# Multiplexers.net
KiCad netlist of a schematic drawn in Altium Designer
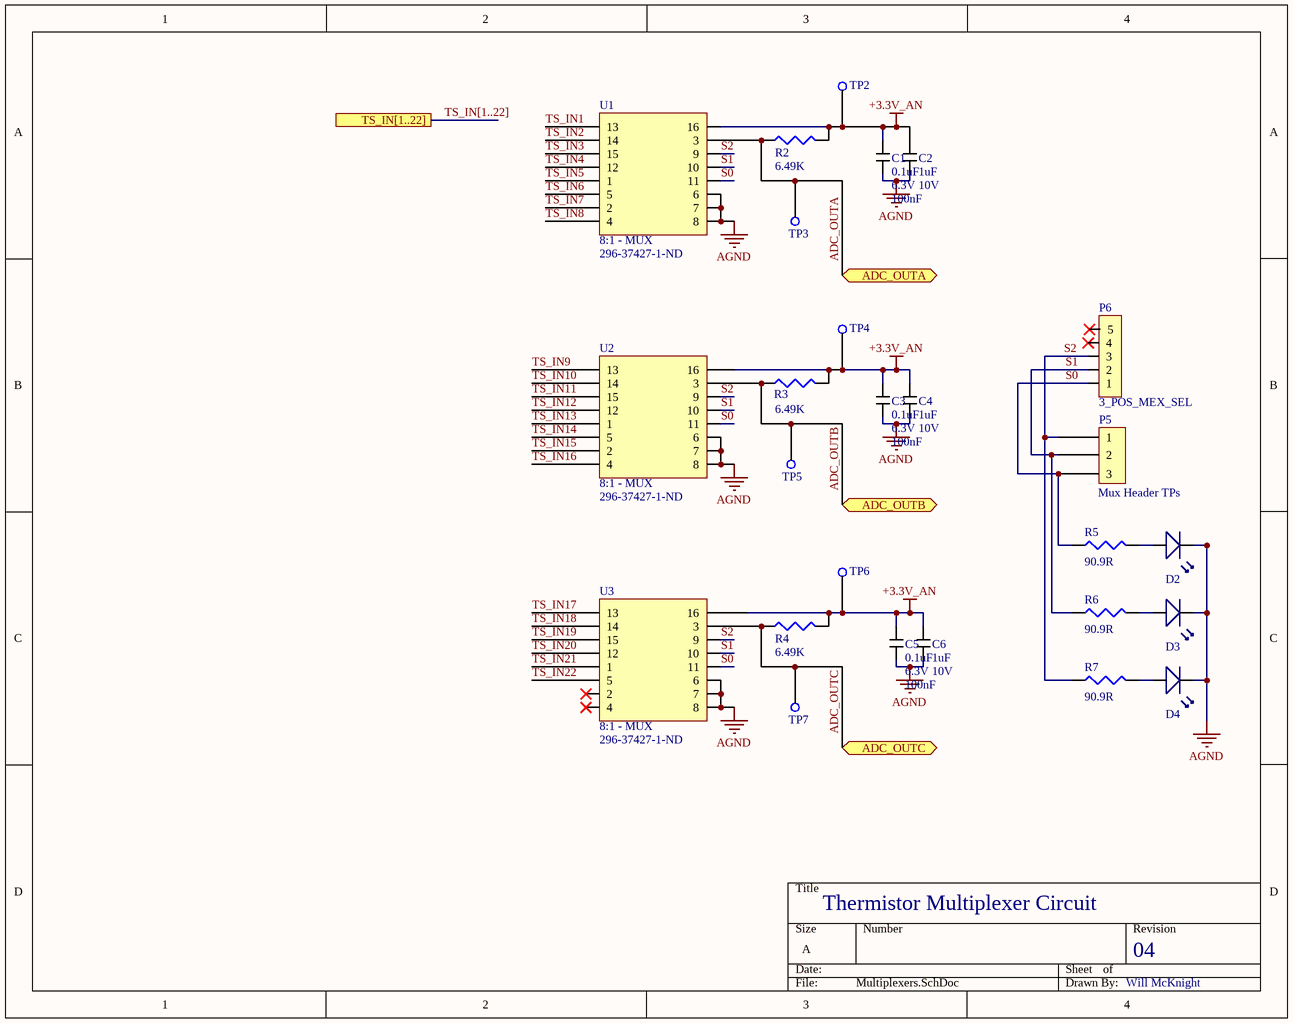
[diagram p0: Multiplexers.SchDoc]

(export (version "E")
  (design (tool "Eeschema 10.0.6"))
  (components
    (comp (ref "C1")
      (value "0.1uF")
      (footprint "0.1uF Bypass Capacitor")
      (description "0.1uF Bypass Cap")
      (fields
        (field (name "MANUFACTURER") "KEMET")
        (field (name "MANUFACTURER PART NUMBER") "C0603C104K9RACTU")
        (field (name "VOLTAGE RATING") "6.3V")
        (field (name "CAPACITANCE") "100nF")
      )
      (libsource (lib "Schematic_Library") (part "0.1uF Cap"))
    )
    (comp (ref "C2")
      (value "1uF")
      (footprint "1UF_SAMSUNG")
      (description "1uF Samsung Cap")
      (fields
        (field (name "MANUFACTURER") "Samsung")
        (field (name "MANUFACTURER PART NUMBER") "CL10B105KP8NNNC")
        (field (name "CAPACITANCE") "1uF")
        (field (name "VOLTAGE RATING") "10V")
      )
      (libsource (lib "Schematic_Library") (part "1uF Samsung Cap"))
    )
    (comp (ref "C3")
      (value "0.1uF")
      (footprint "0.1uF Bypass Capacitor")
      (description "0.1uF Bypass Cap")
      (fields
        (field (name "MANUFACTURER") "KEMET")
        (field (name "MANUFACTURER PART NUMBER") "C0603C104K9RACTU")
        (field (name "VOLTAGE RATING") "6.3V")
        (field (name "CAPACITANCE") "100nF")
      )
      (libsource (lib "Schematic_Library") (part "0.1uF Cap"))
    )
    (comp (ref "C4")
      (value "1uF")
      (footprint "1UF_SAMSUNG")
      (description "1uF Samsung Cap")
      (fields
        (field (name "MANUFACTURER") "Samsung")
        (field (name "MANUFACTURER PART NUMBER") "CL10B105KP8NNNC")
        (field (name "CAPACITANCE") "1uF")
        (field (name "VOLTAGE RATING") "10V")
      )
      (libsource (lib "Schematic_Library") (part "1uF Samsung Cap"))
    )
    (comp (ref "C5")
      (value "0.1uF")
      (footprint "0.1uF Bypass Capacitor")
      (description "0.1uF Bypass Cap")
      (fields
        (field (name "MANUFACTURER") "KEMET")
        (field (name "MANUFACTURER PART NUMBER") "C0603C104K9RACTU")
        (field (name "VOLTAGE RATING") "6.3V")
        (field (name "CAPACITANCE") "100nF")
      )
      (libsource (lib "Schematic_Library") (part "0.1uF Cap"))
    )
    (comp (ref "C6")
      (value "1uF")
      (footprint "1UF_SAMSUNG")
      (description "1uF Samsung Cap")
      (fields
        (field (name "MANUFACTURER") "Samsung")
        (field (name "MANUFACTURER PART NUMBER") "CL10B105KP8NNNC")
        (field (name "CAPACITANCE") "1uF")
        (field (name "VOLTAGE RATING") "10V")
      )
      (libsource (lib "Schematic_Library") (part "1uF Samsung Cap"))
    )
    (comp (ref "D2")
      (value "LED")
      (footprint "Green_SMD_LED")
      (fields
        (field (name "MANUFACTURER") "Dialight")
        (field (name "MANUFACTURER PART NUMBER") "5988070107F")
      )
      (libsource (lib "Schematic_Library") (part "GREEN_LED"))
    )
    (comp (ref "D3")
      (value "LED")
      (footprint "Green_SMD_LED")
      (fields
        (field (name "MANUFACTURER") "Dialight")
        (field (name "MANUFACTURER PART NUMBER") "5988070107F")
      )
      (libsource (lib "Schematic_Library") (part "GREEN_LED"))
    )
    (comp (ref "D4")
      (value "LED")
      (footprint "Green_SMD_LED")
      (fields
        (field (name "MANUFACTURER") "Dialight")
        (field (name "MANUFACTURER PART NUMBER") "5988070107F")
      )
      (libsource (lib "Schematic_Library") (part "GREEN_LED"))
    )
    (comp (ref "P5")
      (value "3 POS Mux Select Header")
      (footprint "Mux Select 3 Pos Header Pin")
      (description "Mux Sel Header TP")
      (fields
        (field (name "MANUFACTURER") "Adam Equipment")
        (field (name "MANUFACTURER PART NUMBER") "PH1RA-03-UA")
      )
      (libsource (lib "Schematic_Library") (part "3 POS Mux Select Header"))
    )
    (comp (ref "P6")
      (value "3_POS_MEX_SEL")
      (footprint "3POS_MUX_SEL")
      (description "Connector Header Surface Mount, Right Angle 3 position 0.049\" (1.25mm)")
      (fields (field (name "MANUFACTURER") "Molex") (field (name "MANUFACTURER PART NUMBER") "505567-0371"))
      (libsource (lib "Schematic_Library") (part "3_POS_MEX_SEL"))
    )
    (comp (ref "R2")
      (value "6.49kOhm SMD Resistor")
      (footprint "RESC2012X06N")
      (fields
        (field (name "MANUFACTURER") "Panasonic")
        (field (name "MANUFACTURER PART NUMBER") "ERA6AEB6491V")
        (field (name "TOLERANCE") "0.1%")
        (field (name "RESISTANCE") "6.49K")
      )
      (libsource (lib "Schematic_Library") (part "6.49kOhm SMD Resistor"))
    )
    (comp (ref "R3")
      (value "6.49kOhm SMD Resistor")
      (footprint "RESC2012X06N")
      (fields
        (field (name "MANUFACTURER") "Panasonic")
        (field (name "MANUFACTURER PART NUMBER") "ERA6AEB6491V")
        (field (name "TOLERANCE") "0.1%")
        (field (name "RESISTANCE") "6.49K")
      )
      (libsource (lib "Schematic_Library") (part "6.49kOhm SMD Resistor"))
    )
    (comp (ref "R4")
      (value "6.49kOhm SMD Resistor")
      (footprint "RESC2012X06N")
      (fields
        (field (name "MANUFACTURER") "Panasonic")
        (field (name "MANUFACTURER PART NUMBER") "ERA6AEB6491V")
        (field (name "TOLERANCE") "0.1%")
        (field (name "RESISTANCE") "6.49K")
      )
      (libsource (lib "Schematic_Library") (part "6.49kOhm SMD Resistor"))
    )
    (comp (ref "R5")
      (value "Green_LED_Res")
      (footprint "Green_LED_Resistor_90.9")
      (fields
        (field (name "MANUFACTURER") "Panasonic")
        (field (name "MANUFACTURER PART NUMBER") "ERJ-1GNF90R9C")
        (field (name "TOLERANCE") "1%")
        (field (name "RESISTANCE") "90.9R")
      )
      (libsource (lib "Schematic_Library") (part "Green_LED_Res"))
    )
    (comp (ref "R6")
      (value "Green_LED_Res")
      (footprint "Green_LED_Resistor_90.9")
      (fields
        (field (name "MANUFACTURER") "Panasonic")
        (field (name "MANUFACTURER PART NUMBER") "ERJ-1GNF90R9C")
        (field (name "TOLERANCE") "1%")
        (field (name "RESISTANCE") "90.9R")
      )
      (libsource (lib "Schematic_Library") (part "Green_LED_Res"))
    )
    (comp (ref "R7")
      (value "Green_LED_Res")
      (footprint "Green_LED_Resistor_90.9")
      (fields
        (field (name "MANUFACTURER") "Panasonic")
        (field (name "MANUFACTURER PART NUMBER") "ERJ-1GNF90R9C")
        (field (name "TOLERANCE") "1%")
        (field (name "RESISTANCE") "90.9R")
      )
      (libsource (lib "Schematic_Library") (part "Green_LED_Res"))
    )
    (comp (ref "TP2")
      (value "Test Point")
      (footprint "Test Point")
      (libsource (lib "Schematic_Library") (part "Test Point"))
    )
    (comp (ref "TP3")
      (value "Test Point")
      (footprint "Test Point")
      (libsource (lib "Schematic_Library") (part "Test Point"))
    )
    (comp (ref "TP4")
      (value "Test Point")
      (footprint "Test Point")
      (libsource (lib "Schematic_Library") (part "Test Point"))
    )
    (comp (ref "TP5")
      (value "Test Point")
      (footprint "Test Point")
      (libsource (lib "Schematic_Library") (part "Test Point"))
    )
    (comp (ref "TP6")
      (value "Test Point")
      (footprint "Test Point")
      (libsource (lib "Schematic_Library") (part "Test Point"))
    )
    (comp (ref "TP7")
      (value "Test Point")
      (footprint "Test Point")
      (libsource (lib "Schematic_Library") (part "Test Point"))
    )
    (comp (ref "U1")
      (value "8:1 - MUX")
      (footprint "8x1 16SOIC MUX")
      (description "Current Therm 8:1 Mux")
      (fields
        (field (name "MANUFACTURER") "Texas Instruments")
        (field (name "MANUFACTURER PART NUMBER") "SN74LV4051ATPWRQ1")
        (field (name "SUPPLIER PART NUMBER 1") "296-37427-1-ND")
      )
      (libsource (lib "Schematic_Library") (part "8{colon}1 - MUX"))
    )
    (comp (ref "U2")
      (value "8:1 - MUX")
      (footprint "8x1 16SOIC MUX")
      (description "Current Therm 8:1 Mux")
      (fields
        (field (name "MANUFACTURER") "Texas Instruments")
        (field (name "MANUFACTURER PART NUMBER") "SN74LV4051ATPWRQ1")
        (field (name "SUPPLIER PART NUMBER 1") "296-37427-1-ND")
      )
      (libsource (lib "Schematic_Library") (part "8{colon}1 - MUX"))
    )
    (comp (ref "U3")
      (value "8:1 - MUX")
      (footprint "8x1 16SOIC MUX")
      (description "Current Therm 8:1 Mux")
      (fields
        (field (name "MANUFACTURER") "Texas Instruments")
        (field (name "MANUFACTURER PART NUMBER") "SN74LV4051ATPWRQ1")
        (field (name "SUPPLIER PART NUMBER 1") "296-37427-1-ND")
      )
      (libsource (lib "Schematic_Library") (part "8{colon}1 - MUX"))
    )
  )
  (nets
    (net (code "1") (name "+3.3V_AN") (class "Default")
      (node (ref "C1") (pin "2") (pinfunction "2_2") (pintype "passive"))
      (node (ref "C2") (pin "2") (pinfunction "2_2") (pintype "passive"))
      (node (ref "C3") (pin "2") (pinfunction "2_2") (pintype "passive"))
      (node (ref "C4") (pin "2") (pinfunction "2_2") (pintype "passive"))
      (node (ref "C5") (pin "2") (pinfunction "2_2") (pintype "passive"))
      (node (ref "C6") (pin "2") (pinfunction "2_2") (pintype "passive"))
      (node (ref "R2") (pin "2") (pinfunction "2_2") (pintype "passive"))
      (node (ref "R3") (pin "2") (pinfunction "2_2") (pintype "passive"))
      (node (ref "R4") (pin "2") (pinfunction "2_2") (pintype "passive"))
      (node (ref "TP2") (pin "1") (pinfunction "1_1") (pintype "passive"))
      (node (ref "TP4") (pin "1") (pinfunction "1_1") (pintype "passive"))
      (node (ref "TP6") (pin "1") (pinfunction "1_1") (pintype "passive"))
      (node (ref "U1") (pin "16") (pinfunction "16_16") (pintype "passive"))
      (node (ref "U2") (pin "16") (pinfunction "16_16") (pintype "passive"))
      (node (ref "U3") (pin "16") (pinfunction "16_16") (pintype "passive"))
    )
    (net (code "2") (name "/ADC_OUTA") (class "Default")
      (node (ref "R2") (pin "1") (pinfunction "1_1") (pintype "passive"))
      (node (ref "TP3") (pin "1") (pinfunction "1_1") (pintype "passive"))
      (node (ref "U1") (pin "3") (pinfunction "3_3") (pintype "passive"))
    )
    (net (code "3") (name "/ADC_OUTB") (class "Default")
      (node (ref "R3") (pin "1") (pinfunction "1_1") (pintype "passive"))
      (node (ref "TP5") (pin "1") (pinfunction "1_1") (pintype "passive"))
      (node (ref "U2") (pin "3") (pinfunction "3_3") (pintype "passive"))
    )
    (net (code "4") (name "/ADC_OUTC") (class "Default")
      (node (ref "R4") (pin "1") (pinfunction "1_1") (pintype "passive"))
      (node (ref "TP7") (pin "1") (pinfunction "1_1") (pintype "passive"))
      (node (ref "U3") (pin "3") (pinfunction "3_3") (pintype "passive"))
    )
    (net (code "5") (name "/S0") (class "Default")
      (node (ref "P5") (pin "3") (pinfunction "3_3") (pintype "passive"))
      (node (ref "P6") (pin "1") (pinfunction "1_1") (pintype "passive"))
      (node (ref "R5") (pin "1") (pinfunction "1_1") (pintype "passive"))
      (node (ref "U1") (pin "11") (pinfunction "11_11") (pintype "passive"))
      (node (ref "U2") (pin "11") (pinfunction "11_11") (pintype "passive"))
      (node (ref "U3") (pin "11") (pinfunction "11_11") (pintype "passive"))
    )
    (net (code "6") (name "/S1") (class "Default")
      (node (ref "P5") (pin "2") (pinfunction "2_2") (pintype "passive"))
      (node (ref "P6") (pin "2") (pinfunction "2_2") (pintype "passive"))
      (node (ref "R6") (pin "1") (pinfunction "1_1") (pintype "passive"))
      (node (ref "U1") (pin "10") (pinfunction "10_10") (pintype "passive"))
      (node (ref "U2") (pin "10") (pinfunction "10_10") (pintype "passive"))
      (node (ref "U3") (pin "10") (pinfunction "10_10") (pintype "passive"))
    )
    (net (code "7") (name "/S2") (class "Default")
      (node (ref "P5") (pin "1") (pinfunction "1_1") (pintype "passive"))
      (node (ref "P6") (pin "3") (pinfunction "3_3") (pintype "passive"))
      (node (ref "R7") (pin "1") (pinfunction "1_1") (pintype "passive"))
      (node (ref "U1") (pin "9") (pinfunction "9_9") (pintype "passive"))
      (node (ref "U2") (pin "9") (pinfunction "9_9") (pintype "passive"))
      (node (ref "U3") (pin "9") (pinfunction "9_9") (pintype "passive"))
    )
    (net (code "8") (name "/TS_IN1") (class "Default")
      (node (ref "U1") (pin "13") (pinfunction "13_13") (pintype "passive"))
    )
    (net (code "9") (name "/TS_IN2") (class "Default")
      (node (ref "U1") (pin "14") (pinfunction "14_14") (pintype "passive"))
    )
    (net (code "10") (name "/TS_IN3") (class "Default")
      (node (ref "U1") (pin "15") (pinfunction "15_15") (pintype "passive"))
    )
    (net (code "11") (name "/TS_IN4") (class "Default")
      (node (ref "U1") (pin "12") (pinfunction "12_12") (pintype "passive"))
    )
    (net (code "12") (name "/TS_IN5") (class "Default")
      (node (ref "U1") (pin "1") (pinfunction "1_1") (pintype "passive"))
    )
    (net (code "13") (name "/TS_IN6") (class "Default")
      (node (ref "U1") (pin "5") (pinfunction "5_5") (pintype "passive"))
    )
    (net (code "14") (name "/TS_IN7") (class "Default")
      (node (ref "U1") (pin "2") (pinfunction "2_2") (pintype "passive"))
    )
    (net (code "15") (name "/TS_IN8") (class "Default")
      (node (ref "U1") (pin "4") (pinfunction "4_4") (pintype "passive"))
    )
    (net (code "16") (name "/TS_IN9") (class "Default")
      (node (ref "U2") (pin "13") (pinfunction "13_13") (pintype "passive"))
    )
    (net (code "17") (name "/TS_IN10") (class "Default")
      (node (ref "U2") (pin "14") (pinfunction "14_14") (pintype "passive"))
    )
    (net (code "18") (name "/TS_IN11") (class "Default")
      (node (ref "U2") (pin "15") (pinfunction "15_15") (pintype "passive"))
    )
    (net (code "19") (name "/TS_IN12") (class "Default")
      (node (ref "U2") (pin "12") (pinfunction "12_12") (pintype "passive"))
    )
    (net (code "20") (name "/TS_IN13") (class "Default")
      (node (ref "U2") (pin "1") (pinfunction "1_1") (pintype "passive"))
    )
    (net (code "21") (name "/TS_IN14") (class "Default")
      (node (ref "U2") (pin "5") (pinfunction "5_5") (pintype "passive"))
    )
    (net (code "22") (name "/TS_IN15") (class "Default")
      (node (ref "U2") (pin "2") (pinfunction "2_2") (pintype "passive"))
    )
    (net (code "23") (name "/TS_IN16") (class "Default")
      (node (ref "U2") (pin "4") (pinfunction "4_4") (pintype "passive"))
    )
    (net (code "24") (name "/TS_IN17") (class "Default")
      (node (ref "U3") (pin "13") (pinfunction "13_13") (pintype "passive"))
    )
    (net (code "25") (name "/TS_IN18") (class "Default")
      (node (ref "U3") (pin "14") (pinfunction "14_14") (pintype "passive"))
    )
    (net (code "26") (name "/TS_IN19") (class "Default")
      (node (ref "U3") (pin "15") (pinfunction "15_15") (pintype "passive"))
    )
    (net (code "27") (name "/TS_IN20") (class "Default")
      (node (ref "U3") (pin "12") (pinfunction "12_12") (pintype "passive"))
    )
    (net (code "28") (name "/TS_IN21") (class "Default")
      (node (ref "U3") (pin "1") (pinfunction "1_1") (pintype "passive"))
    )
    (net (code "29") (name "/TS_IN22") (class "Default")
      (node (ref "U3") (pin "5") (pinfunction "5_5") (pintype "passive"))
    )
    (net (code "31") (name "AGND") (class "Default")
      (node (ref "C1") (pin "1") (pinfunction "1_1") (pintype "passive"))
      (node (ref "C2") (pin "1") (pinfunction "1_1") (pintype "passive"))
      (node (ref "C3") (pin "1") (pinfunction "1_1") (pintype "passive"))
      (node (ref "C4") (pin "1") (pinfunction "1_1") (pintype "passive"))
      (node (ref "C5") (pin "1") (pinfunction "1_1") (pintype "passive"))
      (node (ref "C6") (pin "1") (pinfunction "1_1") (pintype "passive"))
      (node (ref "D2") (pin "1") (pinfunction "1_1") (pintype "passive"))
      (node (ref "D3") (pin "1") (pinfunction "1_1") (pintype "passive"))
      (node (ref "D4") (pin "1") (pinfunction "1_1") (pintype "passive"))
      (node (ref "U1") (pin "6") (pinfunction "6_6") (pintype "passive"))
      (node (ref "U1") (pin "7") (pinfunction "7_7") (pintype "passive"))
      (node (ref "U1") (pin "8") (pinfunction "8_8") (pintype "passive"))
      (node (ref "U2") (pin "6") (pinfunction "6_6") (pintype "passive"))
      (node (ref "U2") (pin "7") (pinfunction "7_7") (pintype "passive"))
      (node (ref "U2") (pin "8") (pinfunction "8_8") (pintype "passive"))
      (node (ref "U3") (pin "6") (pinfunction "6_6") (pintype "passive"))
      (node (ref "U3") (pin "7") (pinfunction "7_7") (pintype "passive"))
      (node (ref "U3") (pin "8") (pinfunction "8_8") (pintype "passive"))
    )
    (net (code "32") (name "Net-(D2-Pad2)") (class "Default")
      (node (ref "D2") (pin "2") (pinfunction "2_2") (pintype "passive"))
      (node (ref "R5") (pin "2") (pinfunction "2_2") (pintype "passive"))
    )
    (net (code "33") (name "Net-(D3-Pad2)") (class "Default")
      (node (ref "D3") (pin "2") (pinfunction "2_2") (pintype "passive"))
      (node (ref "R6") (pin "2") (pinfunction "2_2") (pintype "passive"))
    )
    (net (code "34") (name "Net-(D4-Pad2)") (class "Default")
      (node (ref "D4") (pin "2") (pinfunction "2_2") (pintype "passive"))
      (node (ref "R7") (pin "2") (pinfunction "2_2") (pintype "passive"))
    )
    (net (code "35") (name "unconnected-(P6-Pad4)") (class "Default")
      (node (ref "P6") (pin "4") (pinfunction "4_4") (pintype "passive+no_connect"))
    )
    (net (code "36") (name "unconnected-(P6-Pad5)") (class "Default")
      (node (ref "P6") (pin "5") (pinfunction "5_5") (pintype "passive+no_connect"))
    )
    (net (code "37") (name "unconnected-(U3-Pad2)") (class "Default")
      (node (ref "U3") (pin "2") (pinfunction "2_2") (pintype "passive+no_connect"))
    )
    (net (code "38") (name "unconnected-(U3-Pad4)") (class "Default")
      (node (ref "U3") (pin "4") (pinfunction "4_4") (pintype "passive+no_connect"))
    )
  )
)
